# LED_ONLY_v1.net
KiCad netlist of a schematic drawn in EAGLE
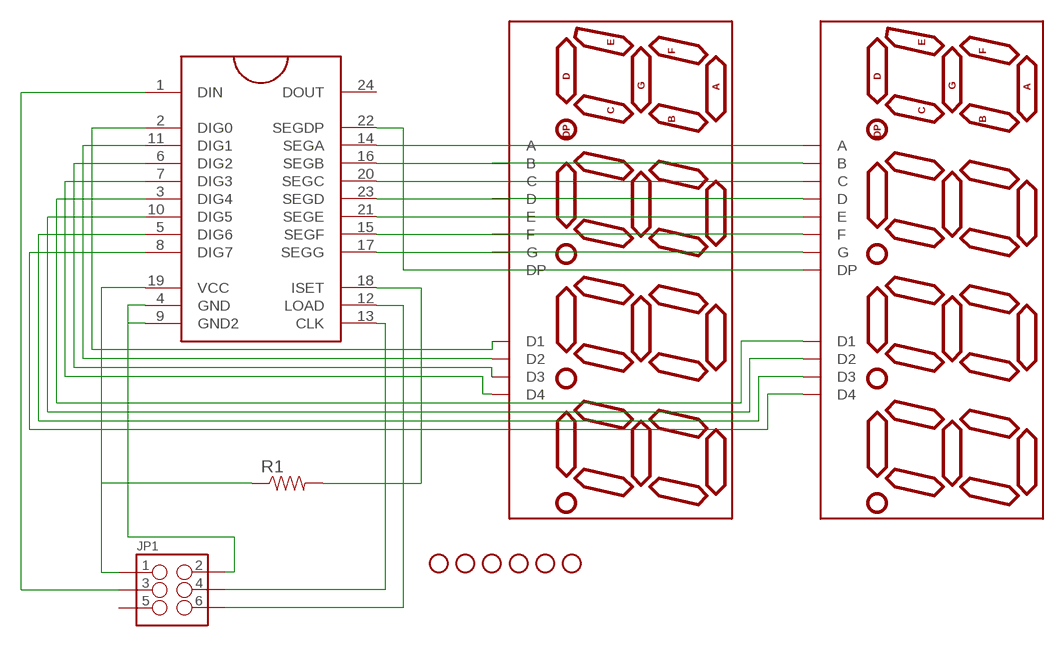
[diagram p0: schematic, sheet 1]

(export (version "E")
  (design (tool "Eeschema 10.0.6"))
  (components
    (comp (ref "JP1")
      (value "M03X2")
      (footprint "eagle-import:2X3-SHROUDED")
      (libsource (lib "eagle-import") (part "M03X2"))
    )
    (comp (ref "R1")
      (value "RESISTORPTH-1/4W")
      (footprint "eagle-import:AXIAL-0.4")
      (libsource (lib "eagle-import") (part "RESISTORPTH-1/4W"))
    )
    (comp (ref "STANDOFF1")
      (value "STAND-OFF")
      (footprint "eagle-import:STAND-OFF")
      (libsource (lib "eagle-import") (part "STAND-OFF"))
    )
    (comp (ref "STANDOFF2")
      (value "STAND-OFF")
      (footprint "eagle-import:STAND-OFF")
      (libsource (lib "eagle-import") (part "STAND-OFF"))
    )
    (comp (ref "STANDOFF3")
      (value "STAND-OFF")
      (footprint "eagle-import:STAND-OFF")
      (libsource (lib "eagle-import") (part "STAND-OFF"))
    )
    (comp (ref "STANDOFF4")
      (value "STAND-OFF")
      (footprint "eagle-import:STAND-OFF")
      (libsource (lib "eagle-import") (part "STAND-OFF"))
    )
    (comp (ref "STANDOFF5")
      (value "STAND-OFF")
      (footprint "eagle-import:STAND-OFF")
      (libsource (lib "eagle-import") (part "STAND-OFF"))
    )
    (comp (ref "STANDOFF6")
      (value "STAND-OFF")
      (footprint "eagle-import:STAND-OFF")
      (libsource (lib "eagle-import") (part "STAND-OFF"))
    )
    (comp (ref "U$3")
      (value "MAX7219DIP")
      (footprint "eagle-import:DIL24")
      (libsource (lib "eagle-import") (part "MAX7219DIP"))
    )
    (comp (ref "U$4")
      (value "7-SEGMENT-4DIGIT-COUNTERPTH")
      (footprint "eagle-import:7-SEGMENT-4DIGIT-COUNTER")
      (libsource (lib "eagle-import") (part "7-SEGMENT-4DIGIT-COUNTERPTH"))
    )
    (comp (ref "U$5")
      (value "7-SEGMENT-4DIGIT-COUNTERPTH")
      (footprint "eagle-import:7-SEGMENT-4DIGIT-COUNTER")
      (libsource (lib "eagle-import") (part "7-SEGMENT-4DIGIT-COUNTERPTH"))
    )
  )
  (nets
    (net (code "1") (name "Net-(R1-1)") (class "Default")
      (node (ref "JP1") (pin "1") (pinfunction "1_1") (pintype "bidirectional"))
      (node (ref "R1") (pin "P$1") (pinfunction "1_P$1") (pintype "passive"))
      (node (ref "U$3") (pin "19") (pinfunction "VCC_19") (pintype "bidirectional"))
    )
    (net (code "2") (name "Net-(R1-2)") (class "Default")
      (node (ref "R1") (pin "P$2") (pinfunction "2_P$2") (pintype "passive"))
      (node (ref "U$3") (pin "18") (pinfunction "ISET_18") (pintype "bidirectional"))
    )
    (net (code "3") (name "Net-(U$3-CLK)") (class "Default")
      (node (ref "JP1") (pin "4") (pinfunction "4_4") (pintype "bidirectional"))
      (node (ref "U$3") (pin "13") (pinfunction "CLK_13") (pintype "bidirectional"))
    )
    (net (code "4") (name "Net-(U$3-DIG0)") (class "Default")
      (node (ref "U$3") (pin "2") (pinfunction "DIG0_2") (pintype "bidirectional"))
      (node (ref "U$4") (pin "12") (pinfunction "D1_12") (pintype "bidirectional"))
    )
    (net (code "5") (name "Net-(U$3-DIG1)") (class "Default")
      (node (ref "U$3") (pin "11") (pinfunction "DIG1_11") (pintype "bidirectional"))
      (node (ref "U$4") (pin "9") (pinfunction "D2_9") (pintype "bidirectional"))
    )
    (net (code "6") (name "Net-(U$3-DIG2)") (class "Default")
      (node (ref "U$3") (pin "6") (pinfunction "DIG2_6") (pintype "bidirectional"))
      (node (ref "U$4") (pin "8") (pinfunction "D3_8") (pintype "bidirectional"))
    )
    (net (code "7") (name "Net-(U$3-DIG3)") (class "Default")
      (node (ref "U$3") (pin "7") (pinfunction "DIG3_7") (pintype "bidirectional"))
      (node (ref "U$4") (pin "6") (pinfunction "D4_6") (pintype "bidirectional"))
    )
    (net (code "8") (name "Net-(U$3-DIG4)") (class "Default")
      (node (ref "U$3") (pin "3") (pinfunction "DIG4_3") (pintype "bidirectional"))
      (node (ref "U$5") (pin "12") (pinfunction "D1_12") (pintype "bidirectional"))
    )
    (net (code "9") (name "Net-(U$3-DIG5)") (class "Default")
      (node (ref "U$3") (pin "10") (pinfunction "DIG5_10") (pintype "bidirectional"))
      (node (ref "U$5") (pin "9") (pinfunction "D2_9") (pintype "bidirectional"))
    )
    (net (code "10") (name "Net-(U$3-DIG6)") (class "Default")
      (node (ref "U$3") (pin "5") (pinfunction "DIG6_5") (pintype "bidirectional"))
      (node (ref "U$5") (pin "8") (pinfunction "D3_8") (pintype "bidirectional"))
    )
    (net (code "11") (name "Net-(U$3-DIG7)") (class "Default")
      (node (ref "U$3") (pin "8") (pinfunction "DIG7_8") (pintype "bidirectional"))
      (node (ref "U$5") (pin "6") (pinfunction "D4_6") (pintype "bidirectional"))
    )
    (net (code "12") (name "Net-(U$3-DIN)") (class "Default")
      (node (ref "JP1") (pin "3") (pinfunction "3_3") (pintype "bidirectional"))
      (node (ref "U$3") (pin "1") (pinfunction "DIN_1") (pintype "bidirectional"))
    )
    (net (code "13") (name "Net-(U$3-GND)") (class "Default")
      (node (ref "JP1") (pin "2") (pinfunction "2_2") (pintype "bidirectional"))
      (node (ref "U$3") (pin "4") (pinfunction "GND_4") (pintype "bidirectional"))
      (node (ref "U$3") (pin "9") (pinfunction "GND2_9") (pintype "bidirectional"))
    )
    (net (code "14") (name "Net-(U$3-LOAD)") (class "Default")
      (node (ref "JP1") (pin "6") (pinfunction "6_6") (pintype "bidirectional"))
      (node (ref "U$3") (pin "12") (pinfunction "LOAD_12") (pintype "bidirectional"))
    )
    (net (code "15") (name "Net-(U$3-SEGA)") (class "Default")
      (node (ref "U$3") (pin "14") (pinfunction "SEGA_14") (pintype "bidirectional"))
      (node (ref "U$4") (pin "11") (pinfunction "A_11") (pintype "bidirectional"))
      (node (ref "U$5") (pin "11") (pinfunction "A_11") (pintype "bidirectional"))
    )
    (net (code "16") (name "Net-(U$3-SEGB)") (class "Default")
      (node (ref "U$3") (pin "16") (pinfunction "SEGB_16") (pintype "bidirectional"))
      (node (ref "U$4") (pin "7") (pinfunction "B_7") (pintype "bidirectional"))
      (node (ref "U$5") (pin "7") (pinfunction "B_7") (pintype "bidirectional"))
    )
    (net (code "17") (name "Net-(U$3-SEGC)") (class "Default")
      (node (ref "U$3") (pin "20") (pinfunction "SEGC_20") (pintype "bidirectional"))
      (node (ref "U$4") (pin "4") (pinfunction "C_4") (pintype "bidirectional"))
      (node (ref "U$5") (pin "4") (pinfunction "C_4") (pintype "bidirectional"))
    )
    (net (code "18") (name "Net-(U$3-SEGD)") (class "Default")
      (node (ref "U$3") (pin "23") (pinfunction "SEGD_23") (pintype "bidirectional"))
      (node (ref "U$4") (pin "2") (pinfunction "D_2") (pintype "bidirectional"))
      (node (ref "U$5") (pin "2") (pinfunction "D_2") (pintype "bidirectional"))
    )
    (net (code "19") (name "Net-(U$3-SEGDP)") (class "Default")
      (node (ref "U$3") (pin "22") (pinfunction "SEGDP_22") (pintype "bidirectional"))
      (node (ref "U$4") (pin "3") (pinfunction "DP_3") (pintype "bidirectional"))
      (node (ref "U$5") (pin "3") (pinfunction "DP_3") (pintype "bidirectional"))
    )
    (net (code "20") (name "Net-(U$3-SEGE)") (class "Default")
      (node (ref "U$3") (pin "21") (pinfunction "SEGE_21") (pintype "bidirectional"))
      (node (ref "U$4") (pin "1") (pinfunction "E_1") (pintype "bidirectional"))
      (node (ref "U$5") (pin "1") (pinfunction "E_1") (pintype "bidirectional"))
    )
    (net (code "21") (name "Net-(U$3-SEGF)") (class "Default")
      (node (ref "U$3") (pin "15") (pinfunction "SEGF_15") (pintype "bidirectional"))
      (node (ref "U$4") (pin "10") (pinfunction "F_10") (pintype "bidirectional"))
      (node (ref "U$5") (pin "10") (pinfunction "F_10") (pintype "bidirectional"))
    )
    (net (code "22") (name "Net-(U$3-SEGG)") (class "Default")
      (node (ref "U$3") (pin "17") (pinfunction "SEGG_17") (pintype "bidirectional"))
      (node (ref "U$4") (pin "5") (pinfunction "G_5") (pintype "bidirectional"))
      (node (ref "U$5") (pin "5") (pinfunction "G_5") (pintype "bidirectional"))
    )
    (net (code "23") (name "unconnected-(JP1-Pad5)") (class "Default")
      (node (ref "JP1") (pin "5") (pinfunction "5_5") (pintype "bidirectional"))
    )
    (net (code "24") (name "unconnected-(U$3-DOUT-Pad24)") (class "Default")
      (node (ref "U$3") (pin "24") (pinfunction "DOUT_24") (pintype "bidirectional"))
    )
  )
)
